# EpyxFastLoad.net
KiCad netlist of a schematic drawn in EAGLE
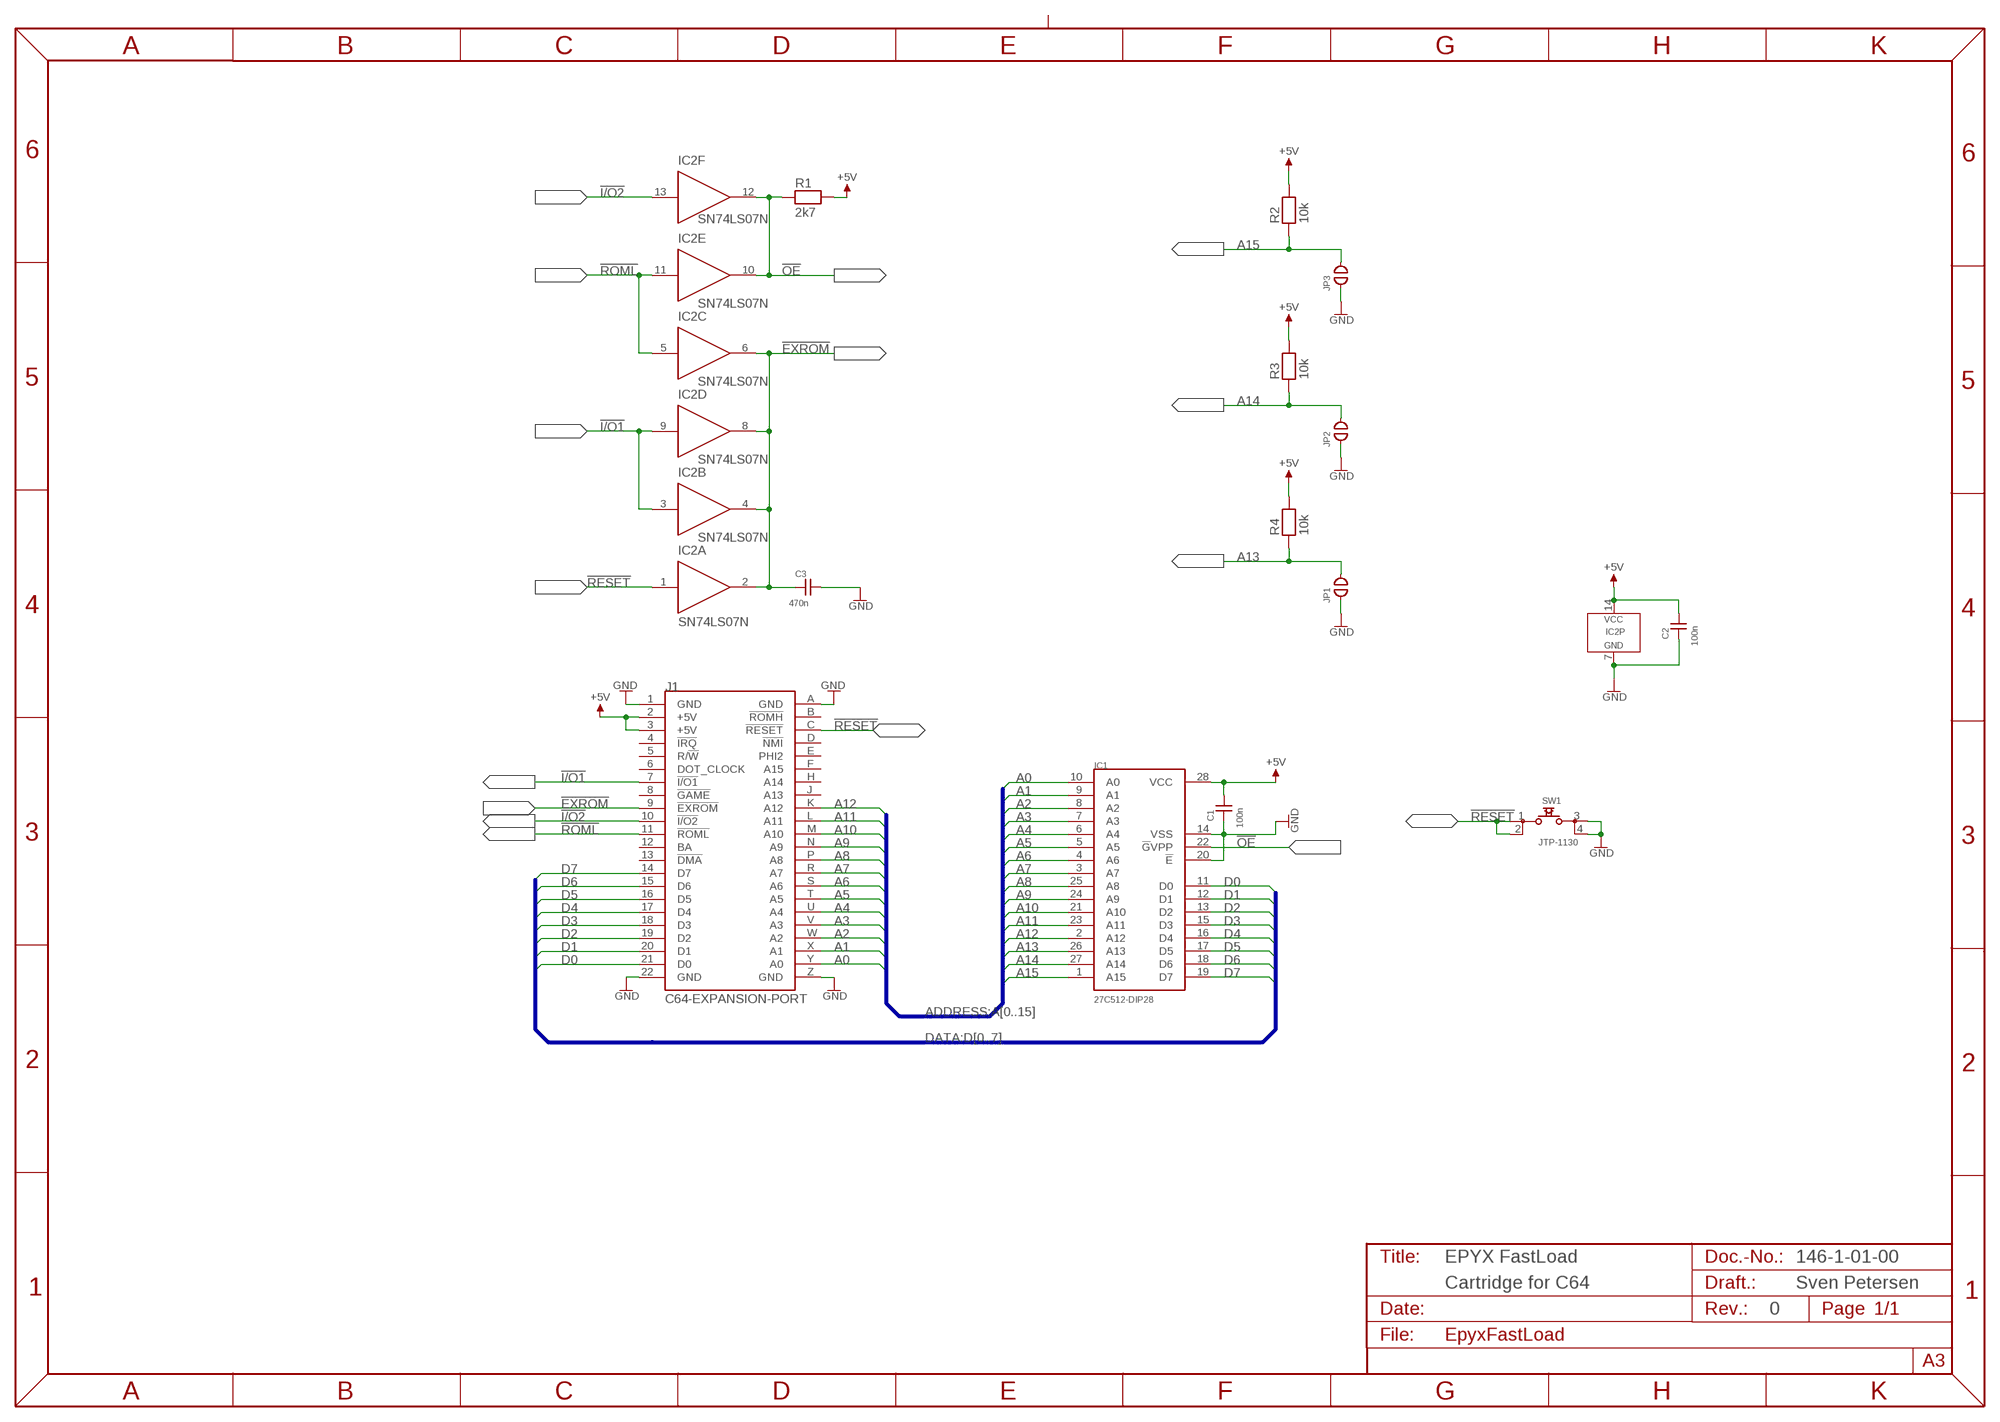
[diagram p0: schematic, sheet 1]

(export (version "E")
  (design (tool "Eeschema 10.0.6"))
  (components
    (comp (ref "C1")
      (value "100n")
      (footprint "eagle-import:C-2,5")
      (libsource (lib "eagle-import") (part "CAP01"))
    )
    (comp (ref "C2")
      (value "100n")
      (footprint "eagle-import:C-2,5")
      (libsource (lib "eagle-import") (part "CAP01"))
    )
    (comp (ref "C3")
      (value "470n")
      (footprint "eagle-import:C-5")
      (libsource (lib "eagle-import") (part "CAP02"))
    )
    (comp (ref "IC1")
      (value "27C512-DIP28")
      (footprint "eagle-import:DIL28-6")
      (libsource (lib "eagle-import") (part "M27C512-DIP28"))
    )
    (comp (ref "IC2")
      (value "SN74LS07N")
      (footprint "eagle-import:DIL-14")
      (libsource (lib "eagle-import") (part "7407N"))
    )
    (comp (ref "J1")
      (value "C64-EXPANSION-PORT")
      (footprint "eagle-import:EXPANSIO_SQ")
      (libsource (lib "eagle-import") (part "C64-EXPANSIONPNARROW"))
    )
    (comp (ref "JP1")
      (value "OPEN")
      (footprint "eagle-import:CP_OP")
      (libsource (lib "eagle-import") (part "OPEN"))
    )
    (comp (ref "JP2")
      (value "OPEN")
      (footprint "eagle-import:CP_OP")
      (libsource (lib "eagle-import") (part "OPEN"))
    )
    (comp (ref "JP3")
      (value "OPEN")
      (footprint "eagle-import:CP_OP")
      (libsource (lib "eagle-import") (part "OPEN"))
    )
    (comp (ref "R1")
      (value "2k7")
      (footprint "eagle-import:R-10")
      (libsource (lib "eagle-import") (part "RES04"))
    )
    (comp (ref "R2")
      (value "10k")
      (footprint "eagle-import:R-10")
      (libsource (lib "eagle-import") (part "RES04"))
    )
    (comp (ref "R3")
      (value "10k")
      (footprint "eagle-import:R-10")
      (libsource (lib "eagle-import") (part "RES04"))
    )
    (comp (ref "R4")
      (value "10k")
      (footprint "eagle-import:R-10")
      (libsource (lib "eagle-import") (part "RES04"))
    )
    (comp (ref "SW1")
      (value "JTP-1130")
      (footprint "eagle-import:JTP-1130")
      (libsource (lib "eagle-import") (part "JTP-1130"))
    )
  )
  (nets
    (net (code "25") (name "+5V") (class "Default")
      (node (ref "C1") (pin "2") (pinfunction "2_2") (pintype "passive"))
      (node (ref "C2") (pin "2") (pinfunction "2_2") (pintype "passive"))
      (node (ref "IC1") (pin "28") (pinfunction "VCC_28") (pintype "power_in"))
      (node (ref "IC2") (pin "14") (pinfunction "VCC_14") (pintype "bidirectional"))
      (node (ref "J1") (pin "2") (pinfunction "+5V_2") (pintype "power_in"))
      (node (ref "J1") (pin "3") (pinfunction "+5V_3") (pintype "power_in"))
      (node (ref "R1") (pin "2") (pinfunction "2_2") (pintype "passive"))
      (node (ref "R2") (pin "2") (pinfunction "2_2") (pintype "passive"))
      (node (ref "R3") (pin "2") (pinfunction "2_2") (pintype "passive"))
      (node (ref "R4") (pin "2") (pinfunction "2_2") (pintype "passive"))
    )
    (net (code "26") (name "/A0") (class "Default")
      (node (ref "IC1") (pin "10") (pinfunction "A0_10") (pintype "input"))
      (node (ref "J1") (pin "Y") (pinfunction "A0_Y") (pintype "bidirectional"))
    )
    (net (code "27") (name "/A1") (class "Default")
      (node (ref "IC1") (pin "9") (pinfunction "A1_9") (pintype "input"))
      (node (ref "J1") (pin "X") (pinfunction "A1_X") (pintype "bidirectional"))
    )
    (net (code "28") (name "/A2") (class "Default")
      (node (ref "IC1") (pin "8") (pinfunction "A2_8") (pintype "input"))
      (node (ref "J1") (pin "W") (pinfunction "A2_W") (pintype "bidirectional"))
    )
    (net (code "29") (name "/A3") (class "Default")
      (node (ref "IC1") (pin "7") (pinfunction "A3_7") (pintype "input"))
      (node (ref "J1") (pin "V") (pinfunction "A3_V") (pintype "bidirectional"))
    )
    (net (code "30") (name "/A4") (class "Default")
      (node (ref "IC1") (pin "6") (pinfunction "A4_6") (pintype "input"))
      (node (ref "J1") (pin "U") (pinfunction "A4_U") (pintype "bidirectional"))
    )
    (net (code "31") (name "/A5") (class "Default")
      (node (ref "IC1") (pin "5") (pinfunction "A5_5") (pintype "input"))
      (node (ref "J1") (pin "T") (pinfunction "A5_T") (pintype "bidirectional"))
    )
    (net (code "32") (name "/A6") (class "Default")
      (node (ref "IC1") (pin "4") (pinfunction "A6_4") (pintype "input"))
      (node (ref "J1") (pin "S") (pinfunction "A6_S") (pintype "bidirectional"))
    )
    (net (code "33") (name "/A7") (class "Default")
      (node (ref "IC1") (pin "3") (pinfunction "A7_3") (pintype "input"))
      (node (ref "J1") (pin "R") (pinfunction "A7_R") (pintype "bidirectional"))
    )
    (net (code "34") (name "/A8") (class "Default")
      (node (ref "IC1") (pin "25") (pinfunction "A8_25") (pintype "input"))
      (node (ref "J1") (pin "P") (pinfunction "A8_P") (pintype "bidirectional"))
    )
    (net (code "35") (name "/A9") (class "Default")
      (node (ref "IC1") (pin "24") (pinfunction "A9_24") (pintype "input"))
      (node (ref "J1") (pin "N") (pinfunction "A9_N") (pintype "bidirectional"))
    )
    (net (code "36") (name "/A10") (class "Default")
      (node (ref "IC1") (pin "21") (pinfunction "A10_21") (pintype "input"))
      (node (ref "J1") (pin "M") (pinfunction "A10_M") (pintype "bidirectional"))
    )
    (net (code "37") (name "/A11") (class "Default")
      (node (ref "IC1") (pin "23") (pinfunction "A11_23") (pintype "input"))
      (node (ref "J1") (pin "L") (pinfunction "A11_L") (pintype "bidirectional"))
    )
    (net (code "38") (name "/A12") (class "Default")
      (node (ref "IC1") (pin "2") (pinfunction "A12_2") (pintype "input"))
      (node (ref "J1") (pin "K") (pinfunction "A12_K") (pintype "bidirectional"))
    )
    (net (code "39") (name "/A13") (class "Default")
      (node (ref "IC1") (pin "26") (pinfunction "A13_26") (pintype "input"))
      (node (ref "JP1") (pin "2") (pinfunction "2_2") (pintype "passive"))
      (node (ref "R4") (pin "1") (pinfunction "1_1") (pintype "passive"))
    )
    (net (code "40") (name "/A14") (class "Default")
      (node (ref "IC1") (pin "27") (pinfunction "A14_27") (pintype "input"))
      (node (ref "JP2") (pin "2") (pinfunction "2_2") (pintype "passive"))
      (node (ref "R3") (pin "1") (pinfunction "1_1") (pintype "passive"))
    )
    (net (code "41") (name "/A15") (class "Default")
      (node (ref "IC1") (pin "1") (pinfunction "A15_1") (pintype "input"))
      (node (ref "JP3") (pin "2") (pinfunction "2_2") (pintype "passive"))
      (node (ref "R2") (pin "1") (pinfunction "1_1") (pintype "passive"))
    )
    (net (code "43") (name "/D0") (class "Default")
      (node (ref "IC1") (pin "11") (pinfunction "D0_11") (pintype "bidirectional"))
      (node (ref "J1") (pin "21") (pinfunction "D0_21") (pintype "bidirectional"))
    )
    (net (code "44") (name "/D1") (class "Default")
      (node (ref "IC1") (pin "12") (pinfunction "D1_12") (pintype "bidirectional"))
      (node (ref "J1") (pin "20") (pinfunction "D1_20") (pintype "bidirectional"))
    )
    (net (code "45") (name "/D2") (class "Default")
      (node (ref "IC1") (pin "13") (pinfunction "D2_13") (pintype "bidirectional"))
      (node (ref "J1") (pin "19") (pinfunction "D2_19") (pintype "bidirectional"))
    )
    (net (code "46") (name "/D3") (class "Default")
      (node (ref "IC1") (pin "15") (pinfunction "D3_15") (pintype "bidirectional"))
      (node (ref "J1") (pin "18") (pinfunction "D3_18") (pintype "bidirectional"))
    )
    (net (code "47") (name "/D4") (class "Default")
      (node (ref "IC1") (pin "16") (pinfunction "D4_16") (pintype "bidirectional"))
      (node (ref "J1") (pin "17") (pinfunction "D4_17") (pintype "bidirectional"))
    )
    (net (code "48") (name "/D5") (class "Default")
      (node (ref "IC1") (pin "17") (pinfunction "D5_17") (pintype "bidirectional"))
      (node (ref "J1") (pin "16") (pinfunction "D5_16") (pintype "bidirectional"))
    )
    (net (code "49") (name "/D6") (class "Default")
      (node (ref "IC1") (pin "18") (pinfunction "D6_18") (pintype "bidirectional"))
      (node (ref "J1") (pin "15") (pinfunction "D6_15") (pintype "bidirectional"))
    )
    (net (code "50") (name "/D7") (class "Default")
      (node (ref "IC1") (pin "19") (pinfunction "D7_19") (pintype "bidirectional"))
      (node (ref "J1") (pin "14") (pinfunction "D7_14") (pintype "bidirectional"))
    )
    (net (code "52") (name "/~{EXROM}") (class "Default")
      (node (ref "C3") (pin "1") (pinfunction "1_1") (pintype "passive"))
      (node (ref "IC2") (pin "2") (pinfunction "O_2") (pintype "open_collector"))
      (node (ref "IC2") (pin "4") (pinfunction "O_4") (pintype "open_collector"))
      (node (ref "IC2") (pin "6") (pinfunction "O_6") (pintype "open_collector"))
      (node (ref "IC2") (pin "8") (pinfunction "O_8") (pintype "open_collector"))
      (node (ref "J1") (pin "9") (pinfunction "~{EXROM}_9") (pintype "input"))
    )
    (net (code "53") (name "/~{I{slash}O1}") (class "Default")
      (node (ref "IC2") (pin "3") (pinfunction "I_3") (pintype "input"))
      (node (ref "IC2") (pin "9") (pinfunction "I_9") (pintype "input"))
      (node (ref "J1") (pin "7") (pinfunction "~{I/O1}_7") (pintype "output"))
    )
    (net (code "54") (name "/~{I{slash}O2}") (class "Default")
      (node (ref "IC2") (pin "13") (pinfunction "I_13") (pintype "input"))
      (node (ref "J1") (pin "10") (pinfunction "~{I/O2}_10") (pintype "output"))
    )
    (net (code "55") (name "/~{OE}") (class "Default")
      (node (ref "IC1") (pin "22") (pinfunction "~{G}VPP_22") (pintype "input"))
      (node (ref "IC2") (pin "10") (pinfunction "O_10") (pintype "open_collector"))
      (node (ref "IC2") (pin "12") (pinfunction "O_12") (pintype "open_collector"))
      (node (ref "R1") (pin "1") (pinfunction "1_1") (pintype "passive"))
    )
    (net (code "56") (name "/~{RESET}") (class "Default")
      (node (ref "IC2") (pin "1") (pinfunction "I_1") (pintype "input"))
      (node (ref "J1") (pin "C") (pinfunction "~{RESET}_C") (pintype "open_collector"))
      (node (ref "SW1") (pin "1") (pinfunction "1_1") (pintype "passive"))
      (node (ref "SW1") (pin "2") (pinfunction "2_2") (pintype "passive"))
    )
    (net (code "57") (name "/~{ROML}") (class "Default")
      (node (ref "IC2") (pin "11") (pinfunction "I_11") (pintype "input"))
      (node (ref "IC2") (pin "5") (pinfunction "I_5") (pintype "input"))
      (node (ref "J1") (pin "11") (pinfunction "~{ROML}_11") (pintype "output"))
    )
    (net (code "58") (name "GND") (class "Default")
      (node (ref "C1") (pin "1") (pinfunction "1_1") (pintype "passive"))
      (node (ref "C2") (pin "1") (pinfunction "1_1") (pintype "passive"))
      (node (ref "C3") (pin "2") (pinfunction "2_2") (pintype "passive"))
      (node (ref "IC1") (pin "14") (pinfunction "VSS_14") (pintype "power_in"))
      (node (ref "IC1") (pin "20") (pinfunction "~{E}_20") (pintype "input"))
      (node (ref "IC2") (pin "7") (pinfunction "GND_7") (pintype "bidirectional"))
      (node (ref "J1") (pin "1") (pinfunction "GND_1") (pintype "power_in"))
      (node (ref "J1") (pin "22") (pinfunction "GND_22") (pintype "power_in"))
      (node (ref "J1") (pin "A") (pinfunction "GND_A") (pintype "power_in"))
      (node (ref "J1") (pin "Z") (pinfunction "GND_Z") (pintype "power_in"))
      (node (ref "JP1") (pin "1") (pinfunction "1_1") (pintype "passive"))
      (node (ref "JP2") (pin "1") (pinfunction "1_1") (pintype "passive"))
      (node (ref "JP3") (pin "1") (pinfunction "1_1") (pintype "passive"))
      (node (ref "SW1") (pin "3") (pinfunction "3_3") (pintype "passive"))
      (node (ref "SW1") (pin "4") (pinfunction "4_4") (pintype "passive"))
    )
    (net (code "59") (name "unconnected-(J1-A13-PadJ)") (class "Default")
      (node (ref "J1") (pin "J") (pinfunction "A13_J") (pintype "bidirectional"))
    )
    (net (code "60") (name "unconnected-(J1-A14-PadH)") (class "Default")
      (node (ref "J1") (pin "H") (pinfunction "A14_H") (pintype "bidirectional"))
    )
    (net (code "61") (name "unconnected-(J1-A15-PadF)") (class "Default")
      (node (ref "J1") (pin "F") (pinfunction "A15_F") (pintype "bidirectional"))
    )
    (net (code "62") (name "unconnected-(J1-BA-Pad12)") (class "Default")
      (node (ref "J1") (pin "12") (pinfunction "BA_12") (pintype "output"))
    )
    (net (code "63") (name "unconnected-(J1-DOT_CLOCK-Pad6)") (class "Default")
      (node (ref "J1") (pin "6") (pinfunction "DOT_CLOCK_6") (pintype "output"))
    )
    (net (code "64") (name "unconnected-(J1-PHI2-PadE)") (class "Default")
      (node (ref "J1") (pin "E") (pinfunction "PHI2_E") (pintype "output"))
    )
    (net (code "65") (name "unconnected-(J1-R{slash}~{W}-Pad5)") (class "Default")
      (node (ref "J1") (pin "5") (pinfunction "R/~{W}_5") (pintype "output"))
    )
    (net (code "66") (name "unconnected-(J1-~{DMA}-Pad13)") (class "Default")
      (node (ref "J1") (pin "13") (pinfunction "~{DMA}_13") (pintype "input"))
    )
    (net (code "67") (name "unconnected-(J1-~{GAME}-Pad8)") (class "Default")
      (node (ref "J1") (pin "8") (pinfunction "~{GAME}_8") (pintype "input"))
    )
    (net (code "68") (name "unconnected-(J1-~{IRQ}-Pad4)") (class "Default")
      (node (ref "J1") (pin "4") (pinfunction "~{IRQ}_4") (pintype "input"))
    )
    (net (code "69") (name "unconnected-(J1-~{NMI}-PadD)") (class "Default")
      (node (ref "J1") (pin "D") (pinfunction "~{NMI}_D") (pintype "input"))
    )
    (net (code "70") (name "unconnected-(J1-~{ROMH}-PadB)") (class "Default")
      (node (ref "J1") (pin "B") (pinfunction "~{ROMH}_B") (pintype "output"))
    )
  )
)
